# garber1.net
KiCad netlist of a schematic drawn in EAGLE
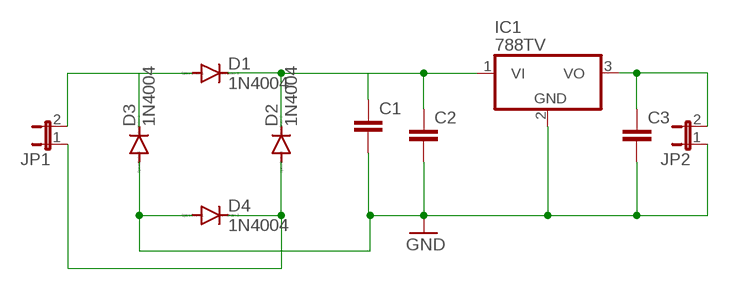
[diagram p0: schematic, sheet 1]

(export (version "E")
  (design (tool "Eeschema 10.0.6"))
  (components
    (comp (ref "C1")
      (value "C2,5-3")
      (footprint "eagle-import:C2.5-3")
      (libsource (lib "eagle-import") (part "C2,5-3"))
    )
    (comp (ref "C2")
      (value "C2,5-3")
      (footprint "eagle-import:C2.5-3")
      (libsource (lib "eagle-import") (part "C2,5-3"))
    )
    (comp (ref "C3")
      (value "C2,5-3")
      (footprint "eagle-import:C2.5-3")
      (libsource (lib "eagle-import") (part "C2,5-3"))
    )
    (comp (ref "D1")
      (value "1N4004")
      (footprint "eagle-import:DO41-10")
      (libsource (lib "eagle-import") (part "1N4004"))
    )
    (comp (ref "D2")
      (value "1N4004")
      (footprint "eagle-import:DO41-10")
      (libsource (lib "eagle-import") (part "1N4004"))
    )
    (comp (ref "D3")
      (value "1N4004")
      (footprint "eagle-import:DO41-10")
      (libsource (lib "eagle-import") (part "1N4004"))
    )
    (comp (ref "D4")
      (value "1N4004")
      (footprint "eagle-import:DO41-10")
      (libsource (lib "eagle-import") (part "1N4004"))
    )
    (comp (ref "IC1")
      (value "788TV")
      (footprint "eagle-import:TO220V")
      (libsource (lib "eagle-import") (part "78TV8"))
    )
    (comp (ref "JP1")
      (value "JP1E")
      (footprint "eagle-import:JP1")
      (libsource (lib "eagle-import") (part "JP1E"))
    )
    (comp (ref "JP2")
      (value "JP1E")
      (footprint "eagle-import:JP1")
      (libsource (lib "eagle-import") (part "JP1E"))
    )
  )
  (nets
    (net (code "1") (name "GND") (class "Default")
      (node (ref "C1") (pin "2") (pinfunction "2_2") (pintype "passive"))
      (node (ref "C2") (pin "2") (pinfunction "2_2") (pintype "passive"))
      (node (ref "C3") (pin "2") (pinfunction "2_2") (pintype "passive"))
      (node (ref "D3") (pin "A") (pinfunction "A_A") (pintype "passive"))
      (node (ref "D4") (pin "A") (pinfunction "A_A") (pintype "passive"))
      (node (ref "IC1") (pin "2") (pinfunction "GND_2") (pintype "passive"))
      (node (ref "JP2") (pin "1") (pinfunction "1_1") (pintype "passive"))
    )
    (net (code "2") (name "Net-(D1-PadA)") (class "Default")
      (node (ref "D1") (pin "A") (pinfunction "A_A") (pintype "passive"))
      (node (ref "D3") (pin "C") (pinfunction "C_C") (pintype "passive"))
      (node (ref "JP1") (pin "2") (pinfunction "2_2") (pintype "passive"))
    )
    (net (code "3") (name "Net-(D2-PadA)") (class "Default")
      (node (ref "D2") (pin "A") (pinfunction "A_A") (pintype "passive"))
      (node (ref "D4") (pin "C") (pinfunction "C_C") (pintype "passive"))
      (node (ref "JP1") (pin "1") (pinfunction "1_1") (pintype "passive"))
    )
    (net (code "4") (name "Net-(IC1-VI)") (class "Default")
      (node (ref "C1") (pin "1") (pinfunction "1_1") (pintype "passive"))
      (node (ref "C2") (pin "1") (pinfunction "1_1") (pintype "passive"))
      (node (ref "D1") (pin "C") (pinfunction "C_C") (pintype "passive"))
      (node (ref "D2") (pin "C") (pinfunction "C_C") (pintype "passive"))
      (node (ref "IC1") (pin "1") (pinfunction "VI_1") (pintype "input"))
    )
    (net (code "5") (name "Net-(IC1-VO)") (class "Default")
      (node (ref "C3") (pin "1") (pinfunction "1_1") (pintype "passive"))
      (node (ref "IC1") (pin "3") (pinfunction "VO_3") (pintype "passive"))
      (node (ref "JP2") (pin "2") (pinfunction "2_2") (pintype "passive"))
    )
  )
)
